# ASBB_ServoIn.net
KiCad netlist of a schematic drawn in Altium Designer
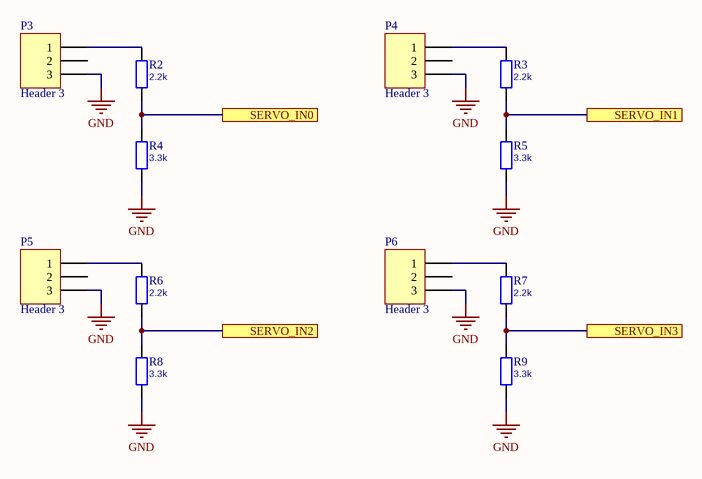
[diagram p0: ASBB_ServoIn.SchDoc]

(export (version "E")
  (design (tool "Eeschema 10.0.6"))
  (components
    (comp (ref "P3")
      (value "Header 3")
      (footprint "HDR1X3")
      (description "Header, 3-Pin")
      (fields (field (name "PUBLISHER") "Altium Limited"))
      (libsource (lib "Miscellaneous Connectors") (part "Header 3"))
    )
    (comp (ref "P4")
      (value "Header 3")
      (footprint "HDR1X3")
      (description "Header, 3-Pin")
      (fields (field (name "PUBLISHER") "Altium Limited"))
      (libsource (lib "Miscellaneous Connectors") (part "Header 3"))
    )
    (comp (ref "P5")
      (value "Header 3")
      (footprint "HDR1X3")
      (description "Header, 3-Pin")
      (fields (field (name "PUBLISHER") "Altium Limited"))
      (libsource (lib "Miscellaneous Connectors") (part "Header 3"))
    )
    (comp (ref "P6")
      (value "Header 3")
      (footprint "HDR1X3")
      (description "Header, 3-Pin")
      (fields (field (name "PUBLISHER") "Altium Limited"))
      (libsource (lib "Miscellaneous Connectors") (part "Header 3"))
    )
    (comp (ref "R2")
      (value "2.2k")
      (footprint "0603")
      (description "Resistor")
      (fields (field (name "PARTNUMBER") "?"))
      (libsource (lib "FZI") (part "Resistor"))
    )
    (comp (ref "R3")
      (value "2.2k")
      (footprint "0603")
      (description "Resistor")
      (fields (field (name "PARTNUMBER") "?"))
      (libsource (lib "FZI") (part "Resistor"))
    )
    (comp (ref "R4")
      (value "3.3k")
      (footprint "0603")
      (description "Resistor")
      (fields (field (name "PARTNUMBER") "?"))
      (libsource (lib "FZI") (part "Resistor"))
    )
    (comp (ref "R5")
      (value "3.3k")
      (footprint "0603")
      (description "Resistor")
      (fields (field (name "PARTNUMBER") "?"))
      (libsource (lib "FZI") (part "Resistor"))
    )
    (comp (ref "R6")
      (value "2.2k")
      (footprint "0603")
      (description "Resistor")
      (fields (field (name "PARTNUMBER") "?"))
      (libsource (lib "FZI") (part "Resistor"))
    )
    (comp (ref "R7")
      (value "2.2k")
      (footprint "0603")
      (description "Resistor")
      (fields (field (name "PARTNUMBER") "?"))
      (libsource (lib "FZI") (part "Resistor"))
    )
    (comp (ref "R8")
      (value "3.3k")
      (footprint "0603")
      (description "Resistor")
      (fields (field (name "PARTNUMBER") "?"))
      (libsource (lib "FZI") (part "Resistor"))
    )
    (comp (ref "R9")
      (value "3.3k")
      (footprint "0603")
      (description "Resistor")
      (fields (field (name "PARTNUMBER") "?"))
      (libsource (lib "FZI") (part "Resistor"))
    )
  )
  (nets
    (net (code "1") (name "/SERVO_IN0") (class "Default")
      (node (ref "R2") (pin "1") (pinfunction "1_1") (pintype "passive"))
      (node (ref "R4") (pin "2") (pinfunction "2_2") (pintype "passive"))
    )
    (net (code "2") (name "/SERVO_IN1") (class "Default")
      (node (ref "R3") (pin "1") (pinfunction "1_1") (pintype "passive"))
      (node (ref "R5") (pin "2") (pinfunction "2_2") (pintype "passive"))
    )
    (net (code "3") (name "/SERVO_IN2") (class "Default")
      (node (ref "R6") (pin "1") (pinfunction "1_1") (pintype "passive"))
      (node (ref "R8") (pin "2") (pinfunction "2_2") (pintype "passive"))
    )
    (net (code "4") (name "/SERVO_IN3") (class "Default")
      (node (ref "R7") (pin "1") (pinfunction "1_1") (pintype "passive"))
      (node (ref "R9") (pin "2") (pinfunction "2_2") (pintype "passive"))
    )
    (net (code "5") (name "GND") (class "Default")
      (node (ref "P3") (pin "3") (pinfunction "3_3") (pintype "passive"))
      (node (ref "P4") (pin "3") (pinfunction "3_3") (pintype "passive"))
      (node (ref "P5") (pin "3") (pinfunction "3_3") (pintype "passive"))
      (node (ref "P6") (pin "3") (pinfunction "3_3") (pintype "passive"))
      (node (ref "R4") (pin "1") (pinfunction "1_1") (pintype "passive"))
      (node (ref "R5") (pin "1") (pinfunction "1_1") (pintype "passive"))
      (node (ref "R8") (pin "1") (pinfunction "1_1") (pintype "passive"))
      (node (ref "R9") (pin "1") (pinfunction "1_1") (pintype "passive"))
    )
    (net (code "6") (name "Net-(P3-Pad1)") (class "Default")
      (node (ref "P3") (pin "1") (pinfunction "1_1") (pintype "passive"))
      (node (ref "R2") (pin "2") (pinfunction "2_2") (pintype "passive"))
    )
    (net (code "7") (name "Net-(P4-Pad1)") (class "Default")
      (node (ref "P4") (pin "1") (pinfunction "1_1") (pintype "passive"))
      (node (ref "R3") (pin "2") (pinfunction "2_2") (pintype "passive"))
    )
    (net (code "8") (name "Net-(P5-Pad1)") (class "Default")
      (node (ref "P5") (pin "1") (pinfunction "1_1") (pintype "passive"))
      (node (ref "R6") (pin "2") (pinfunction "2_2") (pintype "passive"))
    )
    (net (code "9") (name "Net-(P6-Pad1)") (class "Default")
      (node (ref "P6") (pin "1") (pinfunction "1_1") (pintype "passive"))
      (node (ref "R7") (pin "2") (pinfunction "2_2") (pintype "passive"))
    )
    (net (code "10") (name "unconnected-(P3-Pad2)") (class "Default")
      (node (ref "P3") (pin "2") (pinfunction "2_2") (pintype "passive"))
    )
    (net (code "11") (name "unconnected-(P4-Pad2)") (class "Default")
      (node (ref "P4") (pin "2") (pinfunction "2_2") (pintype "passive"))
    )
    (net (code "12") (name "unconnected-(P5-Pad2)") (class "Default")
      (node (ref "P5") (pin "2") (pinfunction "2_2") (pintype "passive"))
    )
    (net (code "13") (name "unconnected-(P6-Pad2)") (class "Default")
      (node (ref "P6") (pin "2") (pinfunction "2_2") (pintype "passive"))
    )
  )
)
